# cpu.net
KiCad netlist of a schematic drawn in Altium Designer
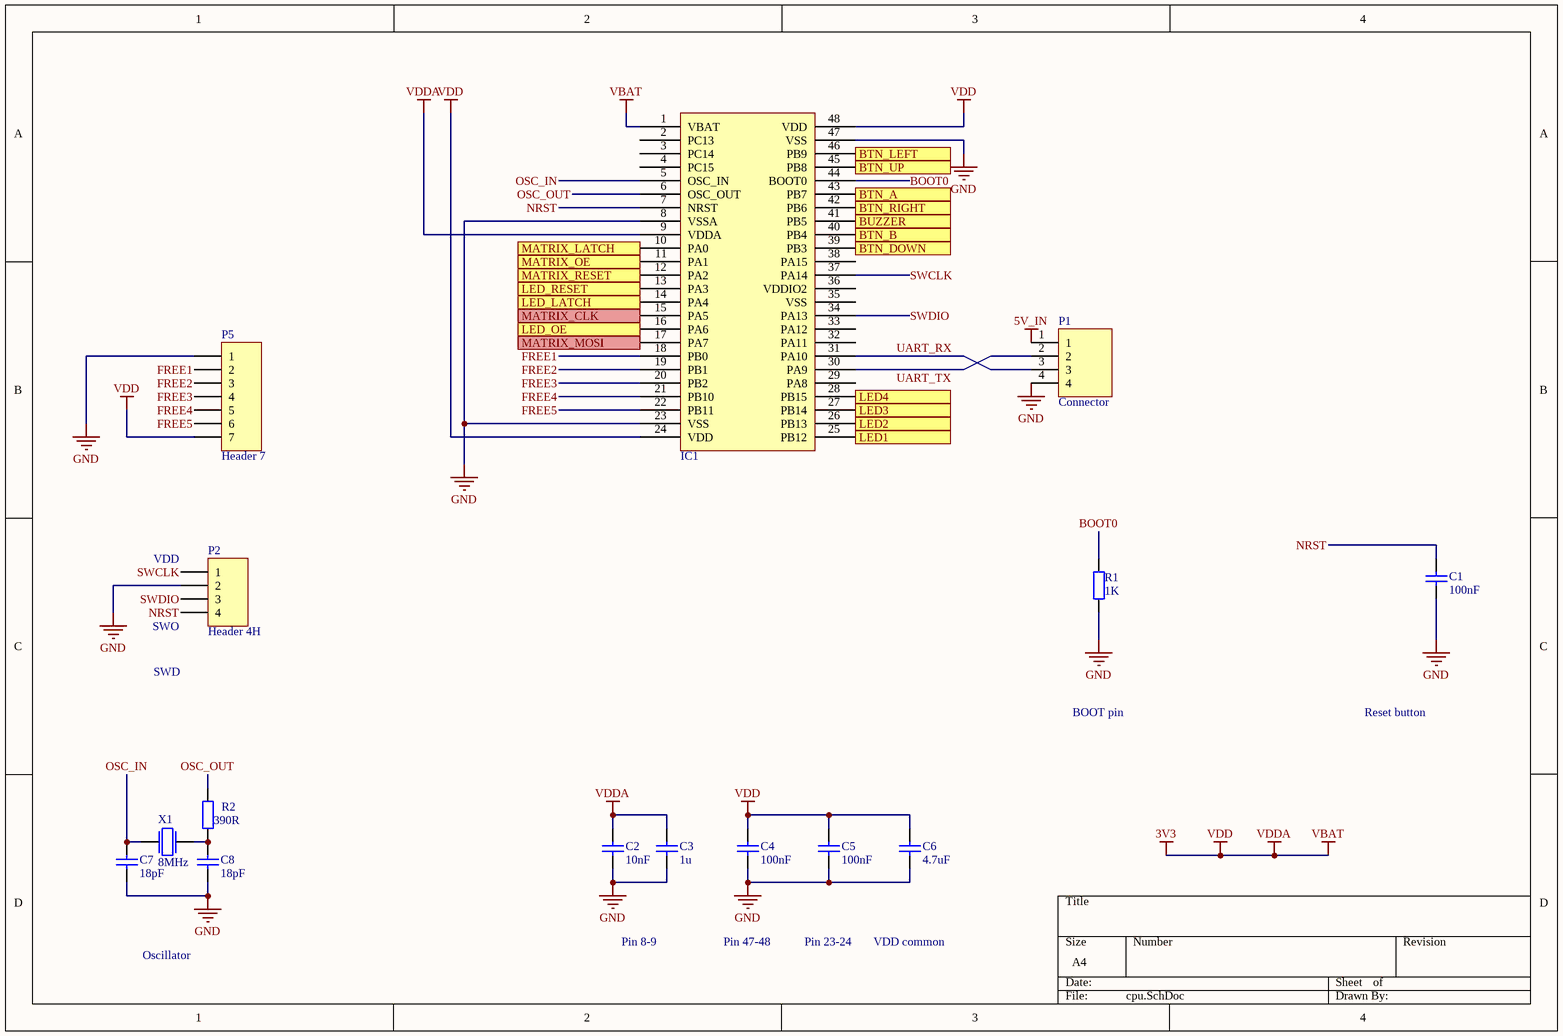
[diagram p0: cpu.SchDoc]

(export (version "E")
  (design (tool "Eeschema 10.0.6"))
  (components
    (comp (ref "C1")
      (value "100nF")
      (footprint "FP_0805_CAP_085")
      (description "Capacitor")
      (fields (field (name "VOLTAGE") "50V"))
      (libsource (lib "hallglib-2018") (part "CAP 100nF"))
    )
    (comp (ref "C2")
      (value "10nF")
      (footprint "FP_0805_CAP_085")
      (description "Capacitor")
      (libsource (lib "hallglib-2018") (part "CAP 10nF"))
    )
    (comp (ref "C3")
      (value "1u")
      (footprint "FP_0805_CAP_085")
      (description "Capacitor")
      (libsource (lib "hallglib") (part "CAP"))
    )
    (comp (ref "C4")
      (value "100nF")
      (footprint "FP_0805_CAP_085")
      (description "Capacitor")
      (fields (field (name "VOLTAGE") "50V"))
      (libsource (lib "hallglib-2018") (part "CAP 100nF"))
    )
    (comp (ref "C5")
      (value "100nF")
      (footprint "FP_0805_CAP_085")
      (description "Capacitor")
      (fields (field (name "VOLTAGE") "50V"))
      (libsource (lib "hallglib-2018") (part "CAP 100nF"))
    )
    (comp (ref "C6")
      (value "4.7uF")
      (footprint "FP_0805_CAP_085")
      (description "Capacitor")
      (libsource (lib "hallglib-2018") (part "CAP 47uF"))
    )
    (comp (ref "C7")
      (value "18pF")
      (footprint "FP_0805_CAP_085")
      (description "Capacitor")
      (libsource (lib "hallglib") (part "CAP"))
    )
    (comp (ref "C8")
      (value "18pF")
      (footprint "FP_0805_CAP_085")
      (description "Capacitor")
      (libsource (lib "hallglib") (part "CAP"))
    )
    (comp (ref "IC1")
      (value "STM32F030C8T6")
      (footprint "LQFP48")
      (description "STM32F030C8T6 ARM MCU")
      (libsource (lib "mb") (part "STM32F030C8T6"))
    )
    (comp (ref "P1")
      (value "Connector")
      (footprint "FP_CONN4_TAP_254MM_90_NOPRINT")
      (description "4pin Connector")
      (libsource (lib "hallglib") (part "Connector_4pin"))
    )
    (comp (ref "P2")
      (value "Header 4H")
      (footprint "HDR1X4")
      (description "Header, 4-Pin, Right Angle")
      (fields (field (name "PUBLISHER") "Altium Limited"))
      (libsource (lib "Miscellaneous Connectors") (part "Header 4H"))
    )
    (comp (ref "P5")
      (value "Header 7")
      (footprint "HDR1X7")
      (description "Header, 7-Pin")
      (fields (field (name "PUBLISHER") "Altium Limited"))
      (libsource (lib "Miscellaneous Connectors") (part "Header 7"))
    )
    (comp (ref "R1")
      (value "1K")
      (footprint "FP_0805_RES")
      (description "Resistor")
      (libsource (lib "hallglib") (part "RES"))
    )
    (comp (ref "R2")
      (value "390R")
      (footprint "FP_0805_RES")
      (description "Resistor")
      (libsource (lib "hallglib-2018") (part "RES 390R"))
    )
    (comp (ref "X1")
      (value "8MHz")
      (footprint "FP_CRYSTAL_HC49")
      (description "Quarz Crystal")
      (libsource (lib "hallglib-2018") (part "Crystal"))
    )
  )
  (nets
    (net (code "1") (name "/BOOT0") (class "Default")
      (node (ref "IC1") (pin "44") (pinfunction "BOOT0_44") (pintype "passive"))
      (node (ref "R1") (pin "2") (pinfunction "2_2") (pintype "passive"))
    )
    (net (code "2") (name "/BTN_A") (class "Default")
      (node (ref "IC1") (pin "43") (pinfunction "PB7_43") (pintype "passive"))
    )
    (net (code "3") (name "/BTN_B") (class "Default")
      (node (ref "IC1") (pin "40") (pinfunction "PB4_40") (pintype "passive"))
    )
    (net (code "4") (name "/BTN_DOWN") (class "Default")
      (node (ref "IC1") (pin "39") (pinfunction "PB3_39") (pintype "passive"))
    )
    (net (code "5") (name "/BTN_LEFT") (class "Default")
      (node (ref "IC1") (pin "46") (pinfunction "PB9_46") (pintype "passive"))
    )
    (net (code "6") (name "/BTN_RIGHT") (class "Default")
      (node (ref "IC1") (pin "42") (pinfunction "PB6_42") (pintype "passive"))
    )
    (net (code "7") (name "/BTN_UP") (class "Default")
      (node (ref "IC1") (pin "45") (pinfunction "PB8_45") (pintype "passive"))
    )
    (net (code "8") (name "/BUZZER") (class "Default")
      (node (ref "IC1") (pin "41") (pinfunction "PB5_41") (pintype "passive"))
    )
    (net (code "9") (name "/FREE1") (class "Default")
      (node (ref "IC1") (pin "18") (pinfunction "PB0_18") (pintype "passive"))
      (node (ref "P5") (pin "2") (pinfunction "2_2") (pintype "passive"))
    )
    (net (code "10") (name "/FREE2") (class "Default")
      (node (ref "IC1") (pin "19") (pinfunction "PB1_19") (pintype "passive"))
      (node (ref "P5") (pin "3") (pinfunction "3_3") (pintype "passive"))
    )
    (net (code "11") (name "/FREE3") (class "Default")
      (node (ref "IC1") (pin "20") (pinfunction "PB2_20") (pintype "passive"))
      (node (ref "P5") (pin "4") (pinfunction "4_4") (pintype "passive"))
    )
    (net (code "12") (name "/FREE4") (class "Default")
      (node (ref "IC1") (pin "21") (pinfunction "PB10_21") (pintype "passive"))
      (node (ref "P5") (pin "5") (pinfunction "5_5") (pintype "passive"))
    )
    (net (code "13") (name "/FREE5") (class "Default")
      (node (ref "IC1") (pin "22") (pinfunction "PB11_22") (pintype "passive"))
      (node (ref "P5") (pin "6") (pinfunction "6_6") (pintype "passive"))
    )
    (net (code "14") (name "/LED1") (class "Default")
      (node (ref "IC1") (pin "25") (pinfunction "PB12_25") (pintype "passive"))
    )
    (net (code "15") (name "/LED2") (class "Default")
      (node (ref "IC1") (pin "26") (pinfunction "PB13_26") (pintype "passive"))
    )
    (net (code "16") (name "/LED3") (class "Default")
      (node (ref "IC1") (pin "27") (pinfunction "PB14_27") (pintype "passive"))
    )
    (net (code "17") (name "/LED4") (class "Default")
      (node (ref "IC1") (pin "28") (pinfunction "PB15_28") (pintype "passive"))
    )
    (net (code "18") (name "/LED_LATCH") (class "Default")
      (node (ref "IC1") (pin "14") (pinfunction "PA4_14") (pintype "passive"))
    )
    (net (code "19") (name "/LED_OE") (class "Default")
      (node (ref "IC1") (pin "16") (pinfunction "PA6_16") (pintype "passive"))
    )
    (net (code "20") (name "/LED_RESET") (class "Default")
      (node (ref "IC1") (pin "13") (pinfunction "PA3_13") (pintype "passive"))
    )
    (net (code "21") (name "/MATRIX_CLK") (class "Default")
      (node (ref "IC1") (pin "15") (pinfunction "PA5_15") (pintype "passive"))
    )
    (net (code "22") (name "/MATRIX_LATCH") (class "Default")
      (node (ref "IC1") (pin "10") (pinfunction "PA0_10") (pintype "passive"))
    )
    (net (code "23") (name "/MATRIX_MOSI") (class "Default")
      (node (ref "IC1") (pin "17") (pinfunction "PA7_17") (pintype "passive"))
    )
    (net (code "24") (name "/MATRIX_OE") (class "Default")
      (node (ref "IC1") (pin "11") (pinfunction "PA1_11") (pintype "passive"))
    )
    (net (code "25") (name "/MATRIX_RESET") (class "Default")
      (node (ref "IC1") (pin "12") (pinfunction "PA2_12") (pintype "passive"))
    )
    (net (code "26") (name "/NRST") (class "Default")
      (node (ref "C1") (pin "2") (pinfunction "2_2") (pintype "passive"))
      (node (ref "IC1") (pin "7") (pinfunction "NRST_7") (pintype "passive"))
      (node (ref "P2") (pin "4") (pinfunction "4_4") (pintype "passive"))
    )
    (net (code "27") (name "/OSC_IN") (class "Default")
      (node (ref "C7") (pin "2") (pinfunction "2_2") (pintype "passive"))
      (node (ref "IC1") (pin "5") (pinfunction "OSC_IN_5") (pintype "passive"))
      (node (ref "X1") (pin "1") (pinfunction "1_1") (pintype "passive"))
    )
    (net (code "28") (name "/OSC_OUT") (class "Default")
      (node (ref "IC1") (pin "6") (pinfunction "OSC_OUT_6") (pintype "passive"))
      (node (ref "R2") (pin "2") (pinfunction "2_2") (pintype "passive"))
    )
    (net (code "29") (name "/SWCLK") (class "Default")
      (node (ref "IC1") (pin "37") (pinfunction "PA14_37") (pintype "passive"))
      (node (ref "P2") (pin "1") (pinfunction "1_1") (pintype "passive"))
    )
    (net (code "30") (name "/SWDIO") (class "Default")
      (node (ref "IC1") (pin "34") (pinfunction "PA13_34") (pintype "passive"))
      (node (ref "P2") (pin "3") (pinfunction "3_3") (pintype "passive"))
    )
    (net (code "31") (name "/UART_RX") (class "Default")
      (node (ref "IC1") (pin "31") (pinfunction "PA10_31") (pintype "passive"))
      (node (ref "P1") (pin "3") (pinfunction "3_3") (pintype "passive"))
    )
    (net (code "32") (name "/UART_TX") (class "Default")
      (node (ref "IC1") (pin "30") (pinfunction "PA9_30") (pintype "passive"))
      (node (ref "P1") (pin "2") (pinfunction "2_2") (pintype "passive"))
    )
    (net (code "33") (name "3V3") (class "Default")
      (node (ref "C2") (pin "2") (pinfunction "2_2") (pintype "passive"))
      (node (ref "C3") (pin "2") (pinfunction "2_2") (pintype "passive"))
      (node (ref "C4") (pin "2") (pinfunction "2_2") (pintype "passive"))
      (node (ref "C5") (pin "2") (pinfunction "2_2") (pintype "passive"))
      (node (ref "C6") (pin "2") (pinfunction "2_2") (pintype "passive"))
      (node (ref "IC1") (pin "1") (pinfunction "VBAT_1") (pintype "passive"))
      (node (ref "IC1") (pin "24") (pinfunction "VDD_24") (pintype "passive"))
      (node (ref "IC1") (pin "48") (pinfunction "VDD_48") (pintype "passive"))
      (node (ref "IC1") (pin "9") (pinfunction "VDDA_9") (pintype "passive"))
      (node (ref "P5") (pin "7") (pinfunction "7_7") (pintype "passive"))
    )
    (net (code "34") (name "5V_IN") (class "Default")
      (node (ref "P1") (pin "1") (pinfunction "1_1") (pintype "passive"))
    )
    (net (code "35") (name "GND") (class "Default")
      (node (ref "C1") (pin "1") (pinfunction "1_1") (pintype "passive"))
      (node (ref "C2") (pin "1") (pinfunction "1_1") (pintype "passive"))
      (node (ref "C3") (pin "1") (pinfunction "1_1") (pintype "passive"))
      (node (ref "C4") (pin "1") (pinfunction "1_1") (pintype "passive"))
      (node (ref "C5") (pin "1") (pinfunction "1_1") (pintype "passive"))
      (node (ref "C6") (pin "1") (pinfunction "1_1") (pintype "passive"))
      (node (ref "C7") (pin "1") (pinfunction "1_1") (pintype "passive"))
      (node (ref "C8") (pin "1") (pinfunction "1_1") (pintype "passive"))
      (node (ref "IC1") (pin "23") (pinfunction "VSS_23") (pintype "passive"))
      (node (ref "IC1") (pin "47") (pinfunction "VSS_47") (pintype "passive"))
      (node (ref "IC1") (pin "8") (pinfunction "VSSA_8") (pintype "passive"))
      (node (ref "P1") (pin "4") (pinfunction "4_4") (pintype "passive"))
      (node (ref "P2") (pin "2") (pinfunction "2_2") (pintype "passive"))
      (node (ref "P5") (pin "1") (pinfunction "1_1") (pintype "passive"))
      (node (ref "R1") (pin "1") (pinfunction "1_1") (pintype "passive"))
    )
    (net (code "36") (name "Net-(C8-Pad2)") (class "Default")
      (node (ref "C8") (pin "2") (pinfunction "2_2") (pintype "passive"))
      (node (ref "R2") (pin "1") (pinfunction "1_1") (pintype "passive"))
      (node (ref "X1") (pin "2") (pinfunction "2_2") (pintype "passive"))
    )
    (net (code "37") (name "unconnected-(IC1-PA8-Pad29)") (class "Default")
      (node (ref "IC1") (pin "29") (pinfunction "PA8_29") (pintype "passive"))
    )
    (net (code "38") (name "unconnected-(IC1-PA11-Pad32)") (class "Default")
      (node (ref "IC1") (pin "32") (pinfunction "PA11_32") (pintype "passive"))
    )
    (net (code "39") (name "unconnected-(IC1-PA12-Pad33)") (class "Default")
      (node (ref "IC1") (pin "33") (pinfunction "PA12_33") (pintype "passive"))
    )
    (net (code "40") (name "unconnected-(IC1-PA15-Pad38)") (class "Default")
      (node (ref "IC1") (pin "38") (pinfunction "PA15_38") (pintype "passive"))
    )
    (net (code "41") (name "unconnected-(IC1-PC13-Pad2)") (class "Default")
      (node (ref "IC1") (pin "2") (pinfunction "PC13_2") (pintype "passive"))
    )
    (net (code "42") (name "unconnected-(IC1-PC14-Pad3)") (class "Default")
      (node (ref "IC1") (pin "3") (pinfunction "PC14_3") (pintype "passive"))
    )
    (net (code "43") (name "unconnected-(IC1-PC15-Pad4)") (class "Default")
      (node (ref "IC1") (pin "4") (pinfunction "PC15_4") (pintype "passive"))
    )
    (net (code "44") (name "unconnected-(IC1-VDDIO2-Pad36)") (class "Default")
      (node (ref "IC1") (pin "36") (pinfunction "VDDIO2_36") (pintype "passive"))
    )
    (net (code "45") (name "unconnected-(IC1-VSS-Pad35)") (class "Default")
      (node (ref "IC1") (pin "35") (pinfunction "VSS_35") (pintype "passive"))
    )
  )
)
